# Sheet1-driver.net
KiCad netlist of a schematic drawn in Altium Designer
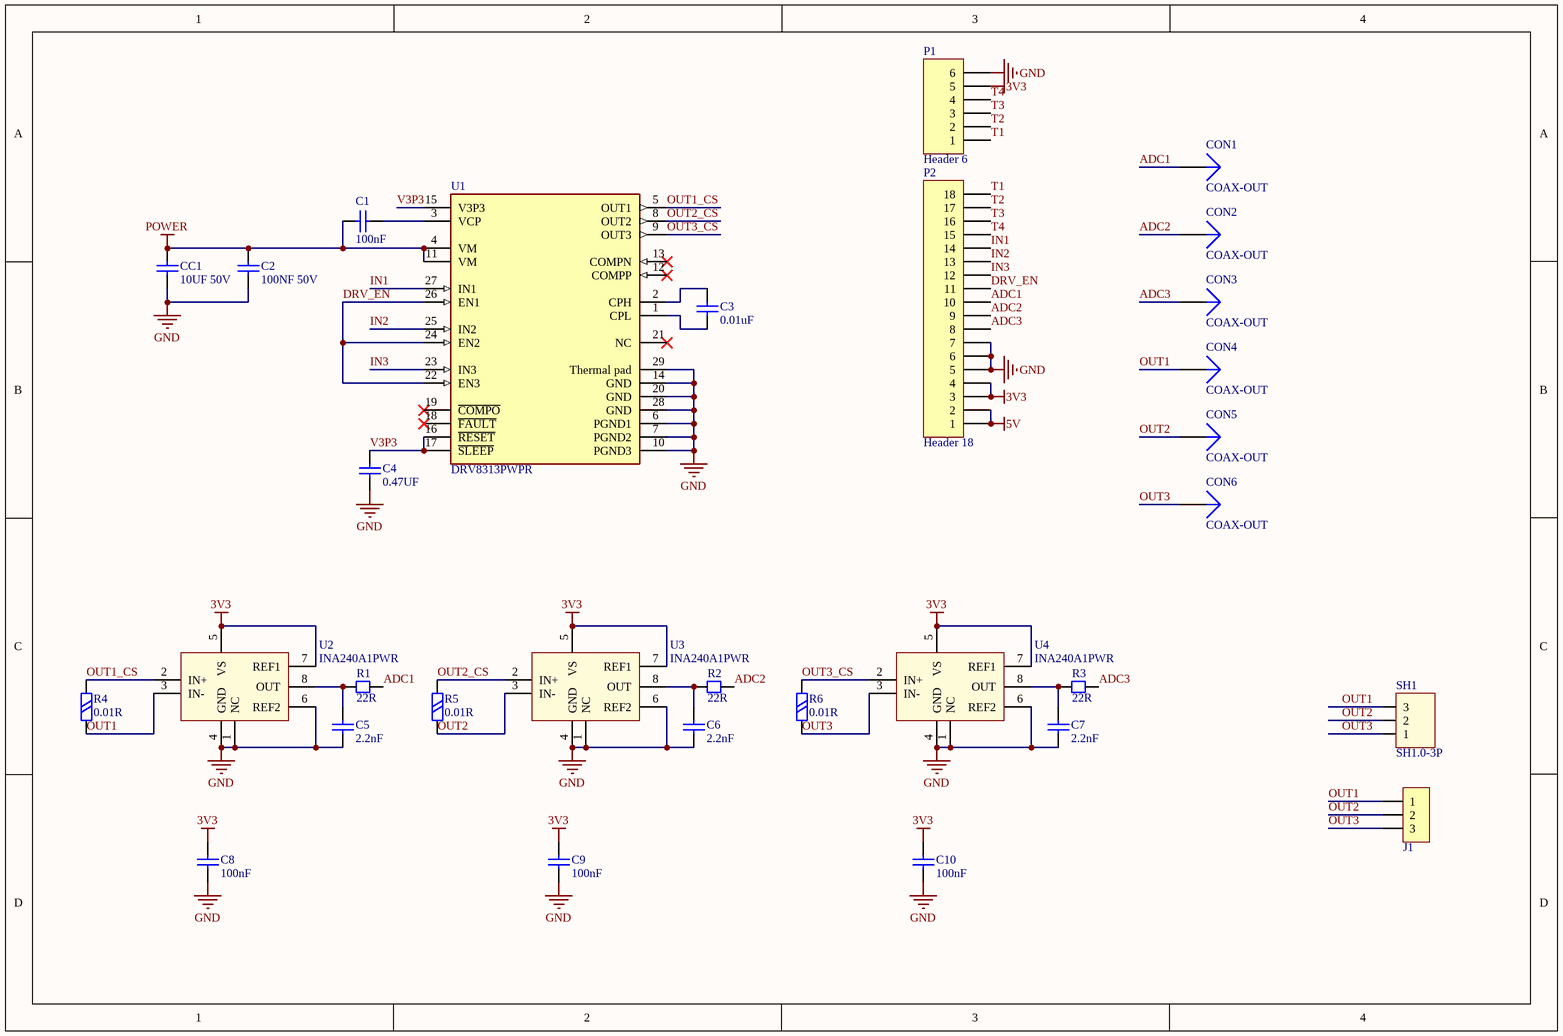
[diagram p0: Sheet1-driver.SchDoc]

(export (version "E")
  (design (tool "Eeschema 10.0.6"))
  (components
    (comp (ref "C1")
      (value "100nF")
      (footprint "CC1608-0603")
      (description "0603封装的电容")
      (fields (field (name "PUBLISHER") "Altium Limited"))
      (libsource (lib "base") (part "Cap Chip 0603"))
    )
    (comp (ref "C2")
      (value "100NF 50V")
      (footprint "CC1608-0603")
      (description "0603封装的电容")
      (fields (field (name "PUBLISHER") "Altium Limited"))
      (libsource (lib "base") (part "Cap Chip 0603"))
    )
    (comp (ref "C3")
      (value "0.01uF")
      (footprint "CC1608-0603")
      (description "0603封装的电容")
      (fields (field (name "PUBLISHER") "Altium Limited"))
      (libsource (lib "base") (part "Cap Chip 0603"))
    )
    (comp (ref "C4")
      (value "0.47UF")
      (footprint "CC1608-0603")
      (description "0603封装的电容")
      (fields (field (name "PUBLISHER") "Altium Limited"))
      (libsource (lib "base") (part "Cap Chip 0603"))
    )
    (comp (ref "C5")
      (value "2.2nF")
      (footprint "CC1608-0603")
      (description "0603封装的电容")
      (fields (field (name "PUBLISHER") "Altium Limited"))
      (libsource (lib "base") (part "Cap Chip 0603"))
    )
    (comp (ref "C6")
      (value "2.2nF")
      (footprint "CC1608-0603")
      (description "0603封装的电容")
      (fields (field (name "PUBLISHER") "Altium Limited"))
      (libsource (lib "base") (part "Cap Chip 0603"))
    )
    (comp (ref "C7")
      (value "2.2nF")
      (footprint "CC1608-0603")
      (description "0603封装的电容")
      (fields (field (name "PUBLISHER") "Altium Limited"))
      (libsource (lib "base") (part "Cap Chip 0603"))
    )
    (comp (ref "C8")
      (value "100nF")
      (footprint "CC1608-0603")
      (description "0603封装的电容")
      (fields (field (name "PUBLISHER") "Altium Limited"))
      (libsource (lib "base") (part "Cap Chip 0603"))
    )
    (comp (ref "C9")
      (value "100nF")
      (footprint "CC1608-0603")
      (description "0603封装的电容")
      (fields (field (name "PUBLISHER") "Altium Limited"))
      (libsource (lib "base") (part "Cap Chip 0603"))
    )
    (comp (ref "C10")
      (value "100nF")
      (footprint "CC1608-0603")
      (description "0603封装的电容")
      (fields (field (name "PUBLISHER") "Altium Limited"))
      (libsource (lib "base") (part "Cap Chip 0603"))
    )
    (comp (ref "CC1")
      (value "10UF 50V")
      (footprint "CC3216-1206")
      (description "Polarized Capacitor (Radial)")
      (fields (field (name "Comment") "Cap Chip 1206") (field (name "PUBLISHER") "Altium Limited"))
      (libsource (lib "base") (part "Cap Chip 1206"))
    )
    (comp (ref "CON1")
      (value "COAX-OUT")
      (footprint "PIN1")
      (description "Coax-M Connector")
      (fields (field (name "PUBLISHER") "Altium Limited"))
      (libsource (lib "Connectors") (part "COAX-OUT"))
    )
    (comp (ref "CON2")
      (value "COAX-OUT")
      (footprint "PIN1")
      (description "Coax-M Connector")
      (fields (field (name "PUBLISHER") "Altium Limited"))
      (libsource (lib "Connectors") (part "COAX-OUT"))
    )
    (comp (ref "CON3")
      (value "COAX-OUT")
      (footprint "PIN1")
      (description "Coax-M Connector")
      (fields (field (name "PUBLISHER") "Altium Limited"))
      (libsource (lib "Connectors") (part "COAX-OUT"))
    )
    (comp (ref "CON4")
      (value "COAX-OUT")
      (footprint "PIN1")
      (description "Coax-M Connector")
      (fields (field (name "PUBLISHER") "Altium Limited"))
      (libsource (lib "Connectors") (part "COAX-OUT"))
    )
    (comp (ref "CON5")
      (value "COAX-OUT")
      (footprint "PIN1")
      (description "Coax-M Connector")
      (fields (field (name "PUBLISHER") "Altium Limited"))
      (libsource (lib "Connectors") (part "COAX-OUT"))
    )
    (comp (ref "CON6")
      (value "COAX-OUT")
      (footprint "PIN1")
      (description "Coax-M Connector")
      (fields (field (name "PUBLISHER") "Altium Limited"))
      (libsource (lib "Connectors") (part "COAX-OUT"))
    )
    (comp (ref "J1")
      (value "HDR-1X3")
      (footprint "KF301-5.0-3P")
      (description "3P拧螺丝插件")
      (fields (field (name "版权归属") "封装库来自淘宝 ID：黄晶宝石"))
      (libsource (lib "Connectors") (part "KF301 3P"))
    )
    (comp (ref "P1")
      (value "Header 6")
      (footprint "HDR1X6")
      (description "Header, 6-Pin")
      (fields (field (name "PUBLISHER") "Altium Limited"))
      (libsource (lib "Connectors") (part "Header 6"))
    )
    (comp (ref "P2")
      (value "Header 18")
      (footprint "HDR1X18")
      (description "Header, 18-Pin")
      (fields (field (name "PUBLISHER") "Altium Limited"))
      (libsource (lib "Connectors") (part "Header 18"))
    )
    (comp (ref "R1")
      (value "22R")
      (footprint "CR1608-0603")
      (description "0603封装电阻")
      (fields (field (name "PUBLISHER") "Altium Limited"))
      (libsource (lib "base") (part "Resistor Chip 0603"))
    )
    (comp (ref "R2")
      (value "22R")
      (footprint "CR1608-0603")
      (description "0603封装电阻")
      (fields (field (name "PUBLISHER") "Altium Limited"))
      (libsource (lib "base") (part "Resistor Chip 0603"))
    )
    (comp (ref "R3")
      (value "22R")
      (footprint "CR1608-0603")
      (description "0603封装电阻")
      (fields (field (name "PUBLISHER") "Altium Limited"))
      (libsource (lib "base") (part "Resistor Chip 0603"))
    )
    (comp (ref "R4")
      (value "0.01R")
      (footprint "CR3216-1206")
      (description "1206封装电阻")
      (fields (field (name "PUBLISHER") "Altium Limited"))
      (libsource (lib "base") (part "Resistor Chip 1206"))
    )
    (comp (ref "R5")
      (value "0.01R")
      (footprint "CR3216-1206")
      (description "1206封装电阻")
      (fields (field (name "PUBLISHER") "Altium Limited"))
      (libsource (lib "base") (part "Resistor Chip 1206"))
    )
    (comp (ref "R6")
      (value "0.01R")
      (footprint "CR3216-1206")
      (description "1206封装电阻")
      (fields (field (name "PUBLISHER") "Altium Limited"))
      (libsource (lib "base") (part "Resistor Chip 1206"))
    )
    (comp (ref "SH1")
      (value "SH1.0-3P")
      (footprint "SH1.0-3P")
      (description "间距为1mm的端子")
      (libsource (lib "Connectors") (part "SH1.0-3P"))
    )
    (comp (ref "U1")
      (value "DRV8313PWPR")
      (footprint "HTSSOP-28")
      (description "独立控制的半 H 桥驱动器,主要用于驱动一个三项无刷电机IC MOTOR DRIVER 8V-60V 28HTSSOP")
      (libsource (lib "PB-Chip") (part "DRV8313"))
    )
    (comp (ref "U2")
      (value "INA240A1PWR")
      (footprint "TSSOP-8")
      (description "超精密电流检测放大器")
      (libsource (lib "power-chip") (part "INA240A1PWR"))
    )
    (comp (ref "U3")
      (value "INA240A1PWR")
      (footprint "TSSOP-8")
      (description "超精密电流检测放大器")
      (libsource (lib "power-chip") (part "INA240A1PWR"))
    )
    (comp (ref "U4")
      (value "INA240A1PWR")
      (footprint "TSSOP-8")
      (description "超精密电流检测放大器")
      (libsource (lib "power-chip") (part "INA240A1PWR"))
    )
  )
  (nets
    (net (code "1") (name "/ADC1") (class "Default")
      (node (ref "CON1") (pin "1") (pinfunction "A_1") (pintype "passive"))
      (node (ref "P2") (pin "10") (pinfunction "10_10") (pintype "passive"))
      (node (ref "R1") (pin "1") (pinfunction "1_1") (pintype "passive"))
    )
    (net (code "2") (name "/ADC2") (class "Default")
      (node (ref "CON2") (pin "1") (pinfunction "A_1") (pintype "passive"))
      (node (ref "P2") (pin "9") (pinfunction "9_9") (pintype "passive"))
      (node (ref "R2") (pin "1") (pinfunction "1_1") (pintype "passive"))
    )
    (net (code "3") (name "/ADC3") (class "Default")
      (node (ref "CON3") (pin "1") (pinfunction "A_1") (pintype "passive"))
      (node (ref "P2") (pin "8") (pinfunction "8_8") (pintype "passive"))
      (node (ref "R3") (pin "1") (pinfunction "1_1") (pintype "passive"))
    )
    (net (code "4") (name "/DRV_EN") (class "Default")
      (node (ref "P2") (pin "11") (pinfunction "11_11") (pintype "passive"))
      (node (ref "U1") (pin "22") (pinfunction "EN3_22") (pintype "input"))
      (node (ref "U1") (pin "24") (pinfunction "EN2_24") (pintype "input"))
      (node (ref "U1") (pin "26") (pinfunction "EN1_26") (pintype "input"))
    )
    (net (code "5") (name "/IN1") (class "Default")
      (node (ref "P2") (pin "14") (pinfunction "14_14") (pintype "passive"))
      (node (ref "U1") (pin "27") (pinfunction "IN1_27") (pintype "input"))
    )
    (net (code "6") (name "/IN2") (class "Default")
      (node (ref "P2") (pin "13") (pinfunction "13_13") (pintype "passive"))
      (node (ref "U1") (pin "25") (pinfunction "IN2_25") (pintype "input"))
    )
    (net (code "7") (name "/IN3") (class "Default")
      (node (ref "P2") (pin "12") (pinfunction "12_12") (pintype "passive"))
      (node (ref "U1") (pin "23") (pinfunction "IN3_23") (pintype "input"))
    )
    (net (code "8") (name "/OUT1") (class "Default")
      (node (ref "CON4") (pin "1") (pinfunction "A_1") (pintype "passive"))
      (node (ref "J1") (pin "1") (pinfunction "1_1") (pintype "passive"))
      (node (ref "R4") (pin "1") (pinfunction "1_1") (pintype "passive"))
      (node (ref "SH1") (pin "3") (pinfunction "3_3") (pintype "passive"))
      (node (ref "U2") (pin "3") (pinfunction "IN-_3") (pintype "passive"))
    )
    (net (code "9") (name "/OUT1_CS") (class "Default")
      (node (ref "R4") (pin "2") (pinfunction "2_2") (pintype "passive"))
      (node (ref "U1") (pin "5") (pinfunction "OUT1_5") (pintype "output"))
      (node (ref "U2") (pin "2") (pinfunction "IN+_2") (pintype "passive"))
    )
    (net (code "10") (name "/OUT2") (class "Default")
      (node (ref "CON5") (pin "1") (pinfunction "A_1") (pintype "passive"))
      (node (ref "J1") (pin "2") (pinfunction "2_2") (pintype "passive"))
      (node (ref "R5") (pin "1") (pinfunction "1_1") (pintype "passive"))
      (node (ref "SH1") (pin "2") (pinfunction "2_2") (pintype "passive"))
      (node (ref "U3") (pin "3") (pinfunction "IN-_3") (pintype "passive"))
    )
    (net (code "11") (name "/OUT2_CS") (class "Default")
      (node (ref "R5") (pin "2") (pinfunction "2_2") (pintype "passive"))
      (node (ref "U1") (pin "8") (pinfunction "OUT2_8") (pintype "output"))
      (node (ref "U3") (pin "2") (pinfunction "IN+_2") (pintype "passive"))
    )
    (net (code "12") (name "/OUT3") (class "Default")
      (node (ref "CON6") (pin "1") (pinfunction "A_1") (pintype "passive"))
      (node (ref "J1") (pin "3") (pinfunction "3_3") (pintype "passive"))
      (node (ref "R6") (pin "1") (pinfunction "1_1") (pintype "passive"))
      (node (ref "SH1") (pin "1") (pinfunction "1_1") (pintype "passive"))
      (node (ref "U4") (pin "3") (pinfunction "IN-_3") (pintype "passive"))
    )
    (net (code "13") (name "/OUT3_CS") (class "Default")
      (node (ref "R6") (pin "2") (pinfunction "2_2") (pintype "passive"))
      (node (ref "U1") (pin "9") (pinfunction "OUT3_9") (pintype "output"))
      (node (ref "U4") (pin "2") (pinfunction "IN+_2") (pintype "passive"))
    )
    (net (code "14") (name "/T1") (class "Default")
      (node (ref "P1") (pin "1") (pinfunction "1_1") (pintype "passive"))
      (node (ref "P2") (pin "18") (pinfunction "18_18") (pintype "passive"))
    )
    (net (code "15") (name "/T2") (class "Default")
      (node (ref "P1") (pin "2") (pinfunction "2_2") (pintype "passive"))
      (node (ref "P2") (pin "17") (pinfunction "17_17") (pintype "passive"))
    )
    (net (code "16") (name "/T3") (class "Default")
      (node (ref "P1") (pin "3") (pinfunction "3_3") (pintype "passive"))
      (node (ref "P2") (pin "16") (pinfunction "16_16") (pintype "passive"))
    )
    (net (code "17") (name "/T4") (class "Default")
      (node (ref "P1") (pin "4") (pinfunction "4_4") (pintype "passive"))
      (node (ref "P2") (pin "15") (pinfunction "15_15") (pintype "passive"))
    )
    (net (code "18") (name "/V3P3") (class "Default")
      (node (ref "C4") (pin "1") (pinfunction "1_1") (pintype "passive"))
      (node (ref "U1") (pin "15") (pinfunction "V3P3_15") (pintype "power_in"))
      (node (ref "U1") (pin "16") (pinfunction "~{RESET}_16") (pintype "passive"))
      (node (ref "U1") (pin "17") (pinfunction "~{SLEEP}_17") (pintype "passive"))
    )
    (net (code "19") (name "3V3") (class "Default")
      (node (ref "C10") (pin "2") (pinfunction "2_2") (pintype "passive"))
      (node (ref "C8") (pin "2") (pinfunction "2_2") (pintype "passive"))
      (node (ref "C9") (pin "2") (pinfunction "2_2") (pintype "passive"))
      (node (ref "P1") (pin "5") (pinfunction "5_5") (pintype "passive"))
      (node (ref "P2") (pin "3") (pinfunction "3_3") (pintype "passive"))
      (node (ref "P2") (pin "4") (pinfunction "4_4") (pintype "passive"))
      (node (ref "U2") (pin "5") (pinfunction "VS_5") (pintype "passive"))
      (node (ref "U2") (pin "7") (pinfunction "REF1_7") (pintype "passive"))
      (node (ref "U3") (pin "5") (pinfunction "VS_5") (pintype "passive"))
      (node (ref "U3") (pin "7") (pinfunction "REF1_7") (pintype "passive"))
      (node (ref "U4") (pin "5") (pinfunction "VS_5") (pintype "passive"))
      (node (ref "U4") (pin "7") (pinfunction "REF1_7") (pintype "passive"))
    )
    (net (code "20") (name "5V") (class "Default")
      (node (ref "P2") (pin "1") (pinfunction "1_1") (pintype "passive"))
      (node (ref "P2") (pin "2") (pinfunction "2_2") (pintype "passive"))
    )
    (net (code "21") (name "GND") (class "Default")
      (node (ref "C10") (pin "1") (pinfunction "1_1") (pintype "passive"))
      (node (ref "C2") (pin "2") (pinfunction "2_2") (pintype "passive"))
      (node (ref "C4") (pin "2") (pinfunction "2_2") (pintype "passive"))
      (node (ref "C5") (pin "1") (pinfunction "1_1") (pintype "passive"))
      (node (ref "C6") (pin "1") (pinfunction "1_1") (pintype "passive"))
      (node (ref "C7") (pin "1") (pinfunction "1_1") (pintype "passive"))
      (node (ref "C8") (pin "1") (pinfunction "1_1") (pintype "passive"))
      (node (ref "C9") (pin "1") (pinfunction "1_1") (pintype "passive"))
      (node (ref "CC1") (pin "1") (pinfunction "1_1") (pintype "passive"))
      (node (ref "P1") (pin "6") (pinfunction "6_6") (pintype "passive"))
      (node (ref "P2") (pin "5") (pinfunction "5_5") (pintype "passive"))
      (node (ref "P2") (pin "6") (pinfunction "6_6") (pintype "passive"))
      (node (ref "P2") (pin "7") (pinfunction "7_7") (pintype "passive"))
      (node (ref "U1") (pin "10") (pinfunction "PGND3_10") (pintype "power_in"))
      (node (ref "U1") (pin "14") (pinfunction "GND_14") (pintype "power_in"))
      (node (ref "U1") (pin "20") (pinfunction "GND_20") (pintype "power_in"))
      (node (ref "U1") (pin "28") (pinfunction "GND_28") (pintype "power_in"))
      (node (ref "U1") (pin "29") (pinfunction "Thermal_pad_29") (pintype "power_in"))
      (node (ref "U1") (pin "6") (pinfunction "PGND1_6") (pintype "power_in"))
      (node (ref "U1") (pin "7") (pinfunction "PGND2_7") (pintype "power_in"))
      (node (ref "U2") (pin "1") (pinfunction "NC_1") (pintype "passive"))
      (node (ref "U2") (pin "4") (pinfunction "GND_4") (pintype "passive"))
      (node (ref "U2") (pin "6") (pinfunction "REF2_6") (pintype "passive"))
      (node (ref "U3") (pin "1") (pinfunction "NC_1") (pintype "passive"))
      (node (ref "U3") (pin "4") (pinfunction "GND_4") (pintype "passive"))
      (node (ref "U3") (pin "6") (pinfunction "REF2_6") (pintype "passive"))
      (node (ref "U4") (pin "1") (pinfunction "NC_1") (pintype "passive"))
      (node (ref "U4") (pin "4") (pinfunction "GND_4") (pintype "passive"))
      (node (ref "U4") (pin "6") (pinfunction "REF2_6") (pintype "passive"))
    )
    (net (code "22") (name "Net-(U1-CPH)") (class "Default")
      (node (ref "C3") (pin "1") (pinfunction "1_1") (pintype "passive"))
      (node (ref "U1") (pin "2") (pinfunction "CPH_2") (pintype "power_in"))
    )
    (net (code "23") (name "Net-(U1-CPL)") (class "Default")
      (node (ref "C3") (pin "2") (pinfunction "2_2") (pintype "passive"))
      (node (ref "U1") (pin "1") (pinfunction "CPL_1") (pintype "power_in"))
    )
    (net (code "24") (name "Net-(U1-VCP)") (class "Default")
      (node (ref "C1") (pin "1") (pinfunction "1_1") (pintype "passive"))
      (node (ref "U1") (pin "3") (pinfunction "VCP_3") (pintype "power_in"))
    )
    (net (code "25") (name "Net-(U2-OUT)") (class "Default")
      (node (ref "C5") (pin "2") (pinfunction "2_2") (pintype "passive"))
      (node (ref "R1") (pin "2") (pinfunction "2_2") (pintype "passive"))
      (node (ref "U2") (pin "8") (pinfunction "OUT_8") (pintype "passive"))
    )
    (net (code "26") (name "Net-(U3-OUT)") (class "Default")
      (node (ref "C6") (pin "2") (pinfunction "2_2") (pintype "passive"))
      (node (ref "R2") (pin "2") (pinfunction "2_2") (pintype "passive"))
      (node (ref "U3") (pin "8") (pinfunction "OUT_8") (pintype "passive"))
    )
    (net (code "27") (name "Net-(U4-OUT)") (class "Default")
      (node (ref "C7") (pin "2") (pinfunction "2_2") (pintype "passive"))
      (node (ref "R3") (pin "2") (pinfunction "2_2") (pintype "passive"))
      (node (ref "U4") (pin "8") (pinfunction "OUT_8") (pintype "passive"))
    )
    (net (code "28") (name "POWER") (class "Default")
      (node (ref "C1") (pin "2") (pinfunction "2_2") (pintype "passive"))
      (node (ref "C2") (pin "1") (pinfunction "1_1") (pintype "passive"))
      (node (ref "CC1") (pin "2") (pinfunction "2_2") (pintype "passive"))
      (node (ref "U1") (pin "11") (pinfunction "VM_11") (pintype "power_in"))
      (node (ref "U1") (pin "4") (pinfunction "VM_4") (pintype "power_in"))
    )
    (net (code "29") (name "unconnected-(U1-COMPN-Pad13)") (class "Default")
      (node (ref "U1") (pin "13") (pinfunction "COMPN_13") (pintype "input+no_connect"))
    )
    (net (code "30") (name "unconnected-(U1-COMPP-Pad12)") (class "Default")
      (node (ref "U1") (pin "12") (pinfunction "COMPP_12") (pintype "input+no_connect"))
    )
    (net (code "31") (name "unconnected-(U1-NC-Pad21)") (class "Default")
      (node (ref "U1") (pin "21") (pinfunction "NC_21") (pintype "passive+no_connect"))
    )
    (net (code "32") (name "unconnected-(U1-~{COMPO}-Pad19)") (class "Default")
      (node (ref "U1") (pin "19") (pinfunction "~{COMPO}_19") (pintype "open_collector+no_connect"))
    )
    (net (code "33") (name "unconnected-(U1-~{FAULT}-Pad18)") (class "Default")
      (node (ref "U1") (pin "18") (pinfunction "~{FAULT}_18") (pintype "open_collector+no_connect"))
    )
  )
)
